# usb.net
KiCad netlist of a schematic drawn in Altium Designer
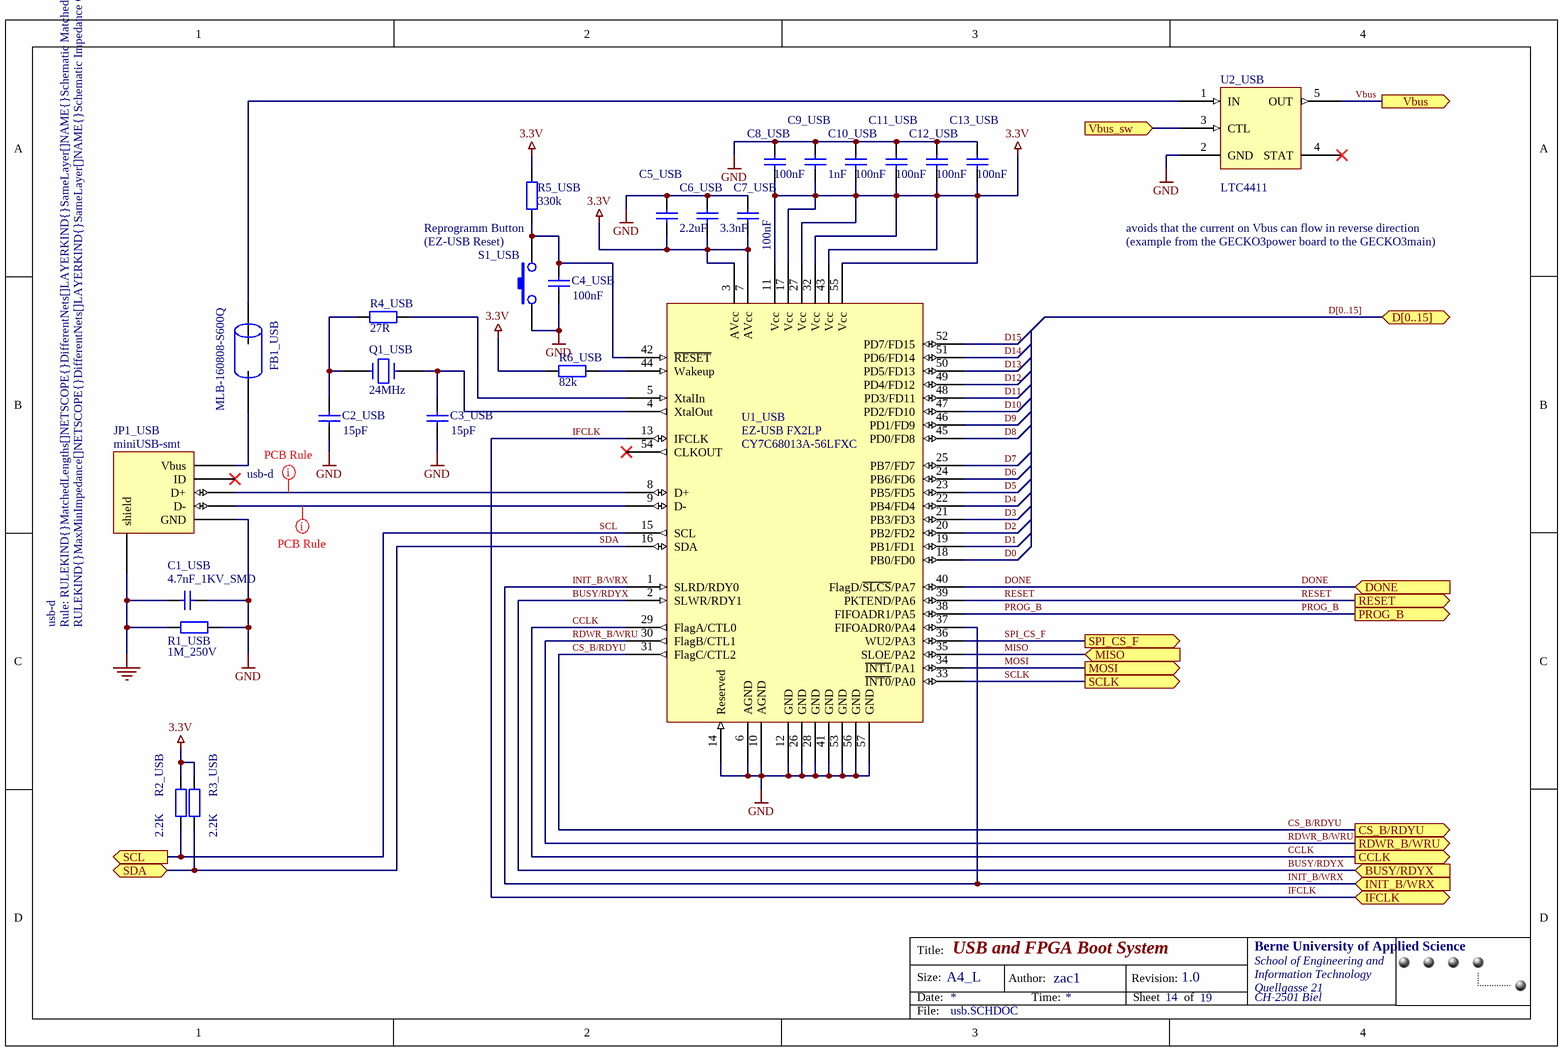
[diagram p0: usb.SCHDOC]

(export (version "E")
  (design (tool "Eeschema 10.0.6"))
  (components
    (comp (ref "C1_USB")
      (value "4.7nF_1KV_SMD")
      (footprint "CC3216-1206")
      (fields
        (field (name "MANUFACTURER") "AVX")
        (field (name "PART NUMBER") "1206AC472KAT1A")
        (field (name "Comment") "C")
      )
      (libsource (lib "gecko3-user") (part "C"))
    )
    (comp (ref "C2_USB")
      (value "15pF")
      (footprint "0402")
      (description "Ceramic Chip Capacitor - Standard")
      (fields
        (field (name "MANUFACTURER") "AVX")
        (field (name "PART NUMBER") "04025A150JAT2A")
        (field (name "PUBLISHER") "Altium Limited")
      )
      (libsource (lib "KEMET Chip Capacitor") (part "C0402"))
    )
    (comp (ref "C3_USB")
      (value "15pF")
      (footprint "0402")
      (description "Ceramic Chip Capacitor - Standard")
      (fields
        (field (name "MANUFACTURER") "AVX")
        (field (name "PART NUMBER") "04025A150JAT2A")
        (field (name "PUBLISHER") "Altium Limited")
      )
      (libsource (lib "KEMET Chip Capacitor") (part "C0402"))
    )
    (comp (ref "C4_USB")
      (value "100nF")
      (footprint "0402")
      (description "Ceramic Chip Capacitor - Standard")
      (fields
        (field (name "MANUFACTURER") "Murata")
        (field (name "PART NUMBER") "GRM155R71C104KA88D")
        (field (name "PUBLISHER") "Altium Limited")
      )
      (libsource (lib "KEMET Chip Capacitor") (part "C0402"))
    )
    (comp (ref "C5_USB")
      (value "2.2uF")
      (footprint "0805")
      (description "Capacitor")
      (fields
        (field (name "MANUFACTURER") "Murata")
        (field (name "PART NUMBER") "GRM21BR71A225KA01L")
        (field (name "PUBLISHER") "Altium Limited")
      )
      (libsource (lib "Miscellaneous Devices") (part "Cap"))
    )
    (comp (ref "C6_USB")
      (value "3.3nF")
      (footprint "0402")
      (description "Capacitor")
      (fields
        (field (name "MANUFACTURER") "PHYCOMP")
        (field (name "PART NUMBER") "2238 587 15629")
        (field (name "PUBLISHER") "Altium Limited")
      )
      (libsource (lib "Miscellaneous Devices") (part "Cap"))
    )
    (comp (ref "C7_USB")
      (value "100nF")
      (footprint "0402")
      (description "Capacitor")
      (fields
        (field (name "MANUFACTURER") "Murata")
        (field (name "PART NUMBER") "GRM155R71C104KA88D")
        (field (name "PUBLISHER") "Altium Limited")
      )
      (libsource (lib "Miscellaneous Devices") (part "Cap"))
    )
    (comp (ref "C8_USB")
      (value "100nF")
      (footprint "0402")
      (description "Capacitor")
      (fields
        (field (name "MANUFACTURER") "Murata")
        (field (name "PART NUMBER") "GRM155R71C104KA88D")
        (field (name "PUBLISHER") "Altium Limited")
      )
      (libsource (lib "Miscellaneous Devices") (part "Cap"))
    )
    (comp (ref "C9_USB")
      (value "1nF")
      (footprint "0402")
      (description "Capacitor")
      (fields
        (field (name "MANUFACTURER") "PHYCOMP")
        (field (name "PART NUMBER") "2238 587 15623")
        (field (name "PUBLISHER") "Altium Limited")
      )
      (libsource (lib "Miscellaneous Devices") (part "Cap"))
    )
    (comp (ref "C10_USB")
      (value "100nF")
      (footprint "0402")
      (description "Capacitor")
      (fields
        (field (name "MANUFACTURER") "Murata")
        (field (name "PART NUMBER") "GRM155R71C104KA88D")
        (field (name "PUBLISHER") "Altium Limited")
      )
      (libsource (lib "Miscellaneous Devices") (part "Cap"))
    )
    (comp (ref "C11_USB")
      (value "100nF")
      (footprint "0402")
      (description "Capacitor")
      (fields
        (field (name "MANUFACTURER") "Murata")
        (field (name "PART NUMBER") "GRM155R71C104KA88D")
        (field (name "PUBLISHER") "Altium Limited")
      )
      (libsource (lib "Miscellaneous Devices") (part "Cap"))
    )
    (comp (ref "C12_USB")
      (value "100nF")
      (footprint "0402")
      (description "Capacitor")
      (fields
        (field (name "MANUFACTURER") "Murata")
        (field (name "PART NUMBER") "GRM155R71C104KA88D")
        (field (name "PUBLISHER") "Altium Limited")
      )
      (libsource (lib "Miscellaneous Devices") (part "Cap"))
    )
    (comp (ref "C13_USB")
      (value "100nF")
      (footprint "0402")
      (description "Capacitor")
      (fields
        (field (name "MANUFACTURER") "Murata")
        (field (name "PART NUMBER") "GRM155R71C104KA88D")
        (field (name "PUBLISHER") "Altium Limited")
      )
      (libsource (lib "Miscellaneous Devices") (part "Cap"))
    )
    (comp (ref "FB1_USB")
      (value "MLB-160808-S600Q")
      (footprint "0603")
      (fields (field (name "MANUFACTURER") "Kitagawa") (field (name "Comment") "FERRITE-BEAD"))
      (libsource (lib "gecko3-user") (part "FERRITE-BEAD"))
    )
    (comp (ref "JP1_USB")
      (value "miniUSB-smt")
      (footprint "USB_MINI_B_SMD")
      (fields
        (field (name "MANUFACTURER") "Lumberg")
        (field (name "PART NUMBER") "2486 01")
        (field (name "Comment") "USB-MINIB-SMT")
      )
      (libsource (lib "gecko3-user") (part "USB-MINIB-SMT"))
    )
    (comp (ref "Q1_USB")
      (value "24MHz")
      (footprint "AT49")
      (description "SMD Quarz in the AT49 Case, like the ABLS series from Abracon")
      (fields
        (field (name "MANUFACTURER") "auris")
        (field (name "PART NUMBER") "Q-24.000M-HC49USSMD-F-30-50-D-30")
      )
      (libsource (lib "gecko3-user") (part "QUARZ-SMD"))
    )
    (comp (ref "R1_USB")
      (value "1M_250V")
      (footprint "CC3216-1206")
      (description "Resistor")
      (fields
        (field (name "MANUFACTURER") "Multicomp")
        (field (name "PART NUMBER") "MC 0.125W 1206 1% 1M")
        (field (name "PUBLISHER") "Altium Limited")
      )
      (libsource (lib "Miscellaneous Devices") (part "Res2"))
    )
    (comp (ref "R2_USB")
      (value "2.2K")
      (footprint "0402")
      (description "Resistor")
      (fields
        (field (name "MANUFACTURER") "PHYCOMP")
        (field (name "PART NUMBER") "232270672202")
        (field (name "PUBLISHER") "Altium Limited")
      )
      (libsource (lib "") (part "Res2_1"))
    )
    (comp (ref "R3_USB")
      (value "2.2K")
      (footprint "0402")
      (description "Resistor")
      (fields
        (field (name "MANUFACTURER") "PHYCOMP")
        (field (name "PART NUMBER") "232270672202")
        (field (name "PUBLISHER") "Altium Limited")
      )
      (libsource (lib "") (part "Res2_1"))
    )
    (comp (ref "R4_USB")
      (value "27R")
      (footprint "0402")
      (description "Resistor")
      (fields
        (field (name "MANUFACTURER") "PHYCOMP")
        (field (name "PART NUMBER") "232270672709")
        (field (name "PUBLISHER") "Altium Limited")
      )
      (libsource (lib "") (part "Res2_2"))
    )
    (comp (ref "R5_USB")
      (value "330k")
      (footprint "0402")
      (description "Resistor")
      (fields
        (field (name "MANUFACTURER") "PHYCOMP")
        (field (name "PART NUMBER") "232270673304")
        (field (name "PUBLISHER") "Altium Limited")
      )
      (libsource (lib "") (part "Res2_1"))
    )
    (comp (ref "R6_USB")
      (value "82k")
      (footprint "0402")
      (description "Resistor")
      (fields
        (field (name "MANUFACTURER") "PHYCOMP")
        (field (name "PART NUMBER") "232270678203")
        (field (name "PUBLISHER") "Altium Limited")
      )
      (libsource (lib "") (part "Res2_2"))
    )
    (comp (ref "S1_USB")
      (value "Reprogramm Button")
      (footprint "FSM")
      (fields (field (name "MANUFACTURER") "TYCO") (field (name "PART NUMBER") "0-1437565-1"))
      (libsource (lib "gecko3-user") (part "SW_PB"))
    )
    (comp (ref "U1_USB")
      (value "EZ-USB FX2LP")
      (footprint "QFN8x8")
      (fields
        (field (name "ALTIUM_VALUE") "CY7C68013A-56LFXC")
        (field (name "MANUFACTURER") "Cypress")
        (field (name "PART NUMBER") "CY7C68013A-56LFXC")
      )
      (libsource (lib "*") (part "EZ-USB-FX2_QFN"))
    )
    (comp (ref "U2_USB")
      (value "LTC4411")
      (footprint "TSOP-23-5")
      (fields (field (name "MANUFACTURER") "Linear") (field (name "PART NUMBER") "LTC4411ES5#PBF"))
      (libsource (lib "gecko3-user") (part "LTC4411"))
    )
  )
  (nets
    (net (code "1") (name "/BUSY{slash}RDYX") (class "Default")
      (node (ref "U1_USB") (pin "2") (pinfunction "SLWR/RDY1_2") (pintype "input"))
    )
    (net (code "2") (name "/CCLK") (class "Default")
      (node (ref "U1_USB") (pin "29") (pinfunction "FlagA/CTL0_29") (pintype "output"))
    )
    (net (code "3") (name "/CS_B{slash}RDYU") (class "Default")
      (node (ref "U1_USB") (pin "31") (pinfunction "FlagC/CTL2_31") (pintype "output"))
    )
    (net (code "4") (name "/D0") (class "Default")
      (node (ref "U1_USB") (pin "18") (pinfunction "PB0/FD0_18") (pintype "bidirectional"))
    )
    (net (code "5") (name "/D1") (class "Default")
      (node (ref "U1_USB") (pin "19") (pinfunction "PB1/FD1_19") (pintype "bidirectional"))
    )
    (net (code "6") (name "/D2") (class "Default")
      (node (ref "U1_USB") (pin "20") (pinfunction "PB2/FD2_20") (pintype "bidirectional"))
    )
    (net (code "7") (name "/D3") (class "Default")
      (node (ref "U1_USB") (pin "21") (pinfunction "PB3/FD3_21") (pintype "bidirectional"))
    )
    (net (code "8") (name "/D4") (class "Default")
      (node (ref "U1_USB") (pin "22") (pinfunction "PB4/FD4_22") (pintype "bidirectional"))
    )
    (net (code "9") (name "/D5") (class "Default")
      (node (ref "U1_USB") (pin "23") (pinfunction "PB5/FD5_23") (pintype "bidirectional"))
    )
    (net (code "10") (name "/D6") (class "Default")
      (node (ref "U1_USB") (pin "24") (pinfunction "PB6/FD6_24") (pintype "bidirectional"))
    )
    (net (code "11") (name "/D7") (class "Default")
      (node (ref "U1_USB") (pin "25") (pinfunction "PB7/FD7_25") (pintype "bidirectional"))
    )
    (net (code "12") (name "/D8") (class "Default")
      (node (ref "U1_USB") (pin "45") (pinfunction "PD0/FD8_45") (pintype "bidirectional"))
    )
    (net (code "13") (name "/D9") (class "Default")
      (node (ref "U1_USB") (pin "46") (pinfunction "PD1/FD9_46") (pintype "bidirectional"))
    )
    (net (code "14") (name "/D10") (class "Default")
      (node (ref "U1_USB") (pin "47") (pinfunction "PD2/FD10_47") (pintype "bidirectional"))
    )
    (net (code "15") (name "/D11") (class "Default")
      (node (ref "U1_USB") (pin "48") (pinfunction "PD3/FD11_48") (pintype "bidirectional"))
    )
    (net (code "16") (name "/D12") (class "Default")
      (node (ref "U1_USB") (pin "49") (pinfunction "PD4/FD12_49") (pintype "bidirectional"))
    )
    (net (code "17") (name "/D13") (class "Default")
      (node (ref "U1_USB") (pin "50") (pinfunction "PD5/FD13_50") (pintype "bidirectional"))
    )
    (net (code "18") (name "/D14") (class "Default")
      (node (ref "U1_USB") (pin "51") (pinfunction "PD6/FD14_51") (pintype "bidirectional"))
    )
    (net (code "19") (name "/D15") (class "Default")
      (node (ref "U1_USB") (pin "52") (pinfunction "PD7/FD15_52") (pintype "bidirectional"))
    )
    (net (code "20") (name "/DONE") (class "Default")
      (node (ref "U1_USB") (pin "40") (pinfunction "FlagD/~{SLCS}/PA7_40") (pintype "bidirectional"))
    )
    (net (code "22") (name "/IFCLK") (class "Default")
      (node (ref "U1_USB") (pin "13") (pinfunction "IFCLK_13") (pintype "bidirectional"))
    )
    (net (code "23") (name "/INIT_B{slash}WRX") (class "Default")
      (node (ref "U1_USB") (pin "1") (pinfunction "SLRD/RDY0_1") (pintype "input"))
      (node (ref "U1_USB") (pin "37") (pinfunction "FIFOADR0/PA4_37") (pintype "bidirectional"))
    )
    (net (code "24") (name "/MISO") (class "Default")
      (node (ref "U1_USB") (pin "35") (pinfunction "SLOE/PA2_35") (pintype "bidirectional"))
    )
    (net (code "25") (name "/MOSI") (class "Default")
      (node (ref "U1_USB") (pin "34") (pinfunction "~{INT1}/PA1_34") (pintype "bidirectional"))
    )
    (net (code "26") (name "/PROG_B") (class "Default")
      (node (ref "U1_USB") (pin "38") (pinfunction "FIFOADR1/PA5_38") (pintype "bidirectional"))
    )
    (net (code "27") (name "/RDWR_B{slash}WRU") (class "Default")
      (node (ref "U1_USB") (pin "30") (pinfunction "FlagB/CTL1_30") (pintype "output"))
    )
    (net (code "28") (name "/RESET") (class "Default")
      (node (ref "U1_USB") (pin "39") (pinfunction "PKTEND/PA6_39") (pintype "bidirectional"))
    )
    (net (code "29") (name "/SCL") (class "Default")
      (node (ref "R2_USB") (pin "1") (pinfunction "1_1") (pintype "passive"))
      (node (ref "U1_USB") (pin "15") (pinfunction "SCL_15") (pintype "output"))
    )
    (net (code "30") (name "/SCLK") (class "Default")
      (node (ref "U1_USB") (pin "33") (pinfunction "~{INT0}/PA0_33") (pintype "bidirectional"))
    )
    (net (code "31") (name "/SDA") (class "Default")
      (node (ref "R3_USB") (pin "1") (pinfunction "1_1") (pintype "passive"))
      (node (ref "U1_USB") (pin "16") (pinfunction "SDA_16") (pintype "bidirectional"))
    )
    (net (code "32") (name "/SPI_CS_F") (class "Default")
      (node (ref "U1_USB") (pin "36") (pinfunction "WU2/PA3_36") (pintype "bidirectional"))
    )
    (net (code "33") (name "/Vbus") (class "Default")
      (node (ref "U2_USB") (pin "5") (pinfunction "OUT_5") (pintype "output"))
    )
    (net (code "34") (name "/Vbus_sw") (class "Default")
      (node (ref "U2_USB") (pin "3") (pinfunction "CTL_3") (pintype "input"))
    )
    (net (code "35") (name "3.3V") (class "Default")
      (node (ref "C10_USB") (pin "1") (pinfunction "1_1") (pintype "passive"))
      (node (ref "C11_USB") (pin "1") (pinfunction "1_1") (pintype "passive"))
      (node (ref "C12_USB") (pin "1") (pinfunction "1_1") (pintype "passive"))
      (node (ref "C13_USB") (pin "1") (pinfunction "1_1") (pintype "passive"))
      (node (ref "C5_USB") (pin "1") (pinfunction "1_1") (pintype "passive"))
      (node (ref "C6_USB") (pin "1") (pinfunction "1_1") (pintype "passive"))
      (node (ref "C7_USB") (pin "1") (pinfunction "1_1") (pintype "passive"))
      (node (ref "C8_USB") (pin "1") (pinfunction "1_1") (pintype "passive"))
      (node (ref "C9_USB") (pin "1") (pinfunction "1_1") (pintype "passive"))
      (node (ref "R2_USB") (pin "2") (pinfunction "2_2") (pintype "passive"))
      (node (ref "R3_USB") (pin "2") (pinfunction "2_2") (pintype "passive"))
      (node (ref "R5_USB") (pin "2") (pinfunction "2_2") (pintype "passive"))
      (node (ref "R6_USB") (pin "2") (pinfunction "2_2") (pintype "passive"))
      (node (ref "U1_USB") (pin "11") (pinfunction "Vcc_11") (pintype "power_in"))
      (node (ref "U1_USB") (pin "17") (pinfunction "Vcc_17") (pintype "power_in"))
      (node (ref "U1_USB") (pin "27") (pinfunction "Vcc_27") (pintype "power_in"))
      (node (ref "U1_USB") (pin "3") (pinfunction "AVcc_3") (pintype "power_in"))
      (node (ref "U1_USB") (pin "32") (pinfunction "Vcc_32") (pintype "power_in"))
      (node (ref "U1_USB") (pin "43") (pinfunction "Vcc_43") (pintype "power_in"))
      (node (ref "U1_USB") (pin "55") (pinfunction "Vcc_55") (pintype "power_in"))
      (node (ref "U1_USB") (pin "7") (pinfunction "AVcc_7") (pintype "power_in"))
    )
    (net (code "36") (name "Earth") (class "Default")
      (node (ref "C1_USB") (pin "1") (pinfunction "1_1") (pintype "passive"))
      (node (ref "JP1_USB") (pin "shield") (pinfunction "shield_shield") (pintype "passive"))
      (node (ref "R1_USB") (pin "1") (pinfunction "1_1") (pintype "passive"))
    )
    (net (code "37") (name "GND") (class "Default")
      (node (ref "C10_USB") (pin "2") (pinfunction "2_2") (pintype "passive"))
      (node (ref "C11_USB") (pin "2") (pinfunction "2_2") (pintype "passive"))
      (node (ref "C12_USB") (pin "2") (pinfunction "2_2") (pintype "passive"))
      (node (ref "C13_USB") (pin "2") (pinfunction "2_2") (pintype "passive"))
      (node (ref "C1_USB") (pin "2") (pinfunction "2_2") (pintype "passive"))
      (node (ref "C2_USB") (pin "1") (pinfunction "1_1") (pintype "passive"))
      (node (ref "C3_USB") (pin "1") (pinfunction "1_1") (pintype "passive"))
      (node (ref "C4_USB") (pin "1") (pinfunction "1_1") (pintype "passive"))
      (node (ref "C5_USB") (pin "2") (pinfunction "2_2") (pintype "passive"))
      (node (ref "C6_USB") (pin "2") (pinfunction "2_2") (pintype "passive"))
      (node (ref "C7_USB") (pin "2") (pinfunction "2_2") (pintype "passive"))
      (node (ref "C8_USB") (pin "2") (pinfunction "2_2") (pintype "passive"))
      (node (ref "C9_USB") (pin "2") (pinfunction "2_2") (pintype "passive"))
      (node (ref "JP1_USB") (pin "GND") (pinfunction "GND_GND") (pintype "power_in"))
      (node (ref "R1_USB") (pin "2") (pinfunction "2_2") (pintype "passive"))
      (node (ref "S1_USB") (pin "1") (pinfunction "1_1") (pintype "passive"))
      (node (ref "U1_USB") (pin "10") (pinfunction "AGND_10") (pintype "power_in"))
      (node (ref "U1_USB") (pin "12") (pinfunction "GND_12") (pintype "power_in"))
      (node (ref "U1_USB") (pin "14") (pinfunction "Reserved_14") (pintype "input"))
      (node (ref "U1_USB") (pin "26") (pinfunction "GND_26") (pintype "power_in"))
      (node (ref "U1_USB") (pin "28") (pinfunction "GND_28") (pintype "power_in"))
      (node (ref "U1_USB") (pin "41") (pinfunction "GND_41") (pintype "power_in"))
      (node (ref "U1_USB") (pin "53") (pinfunction "GND_53") (pintype "power_in"))
      (node (ref "U1_USB") (pin "56") (pinfunction "GND_56") (pintype "power_in"))
      (node (ref "U1_USB") (pin "57") (pinfunction "GND_57") (pintype "power_in"))
      (node (ref "U1_USB") (pin "6") (pinfunction "AGND_6") (pintype "power_in"))
      (node (ref "U2_USB") (pin "2") (pinfunction "GND_2") (pintype "power_in"))
    )
    (net (code "38") (name "Net-(C2_USB-Pad2)") (class "Default")
      (node (ref "C2_USB") (pin "2") (pinfunction "2_2") (pintype "passive"))
      (node (ref "Q1_USB") (pin "1") (pinfunction "1_1") (pintype "passive"))
      (node (ref "R4_USB") (pin "2") (pinfunction "2_2") (pintype "passive"))
    )
    (net (code "39") (name "Net-(FB1_USB-Pad1)") (class "Default")
      (node (ref "FB1_USB") (pin "1") (pinfunction "1_1") (pintype "passive"))
      (node (ref "JP1_USB") (pin "Vbus") (pinfunction "Vbus_Vbus") (pintype "power_in"))
    )
    (net (code "40") (name "Net-(U1_USB-D+)") (class "Default")
      (node (ref "JP1_USB") (pin "D+") (pinfunction "D+_D+") (pintype "bidirectional"))
      (node (ref "U1_USB") (pin "8") (pinfunction "D+_8") (pintype "bidirectional"))
    )
    (net (code "41") (name "Net-(U1_USB-D-)") (class "Default")
      (node (ref "JP1_USB") (pin "D-") (pinfunction "D-_D-") (pintype "bidirectional"))
      (node (ref "U1_USB") (pin "9") (pinfunction "D-_9") (pintype "bidirectional"))
    )
    (net (code "42") (name "Net-(U1_USB-Wakeup)") (class "Default")
      (node (ref "R6_USB") (pin "1") (pinfunction "1_1") (pintype "passive"))
      (node (ref "U1_USB") (pin "44") (pinfunction "Wakeup_44") (pintype "input"))
    )
    (net (code "43") (name "Net-(U1_USB-XtalIn)") (class "Default")
      (node (ref "R4_USB") (pin "1") (pinfunction "1_1") (pintype "passive"))
      (node (ref "U1_USB") (pin "5") (pinfunction "XtalIn_5") (pintype "input"))
    )
    (net (code "44") (name "Net-(U1_USB-XtalOut)") (class "Default")
      (node (ref "C3_USB") (pin "2") (pinfunction "2_2") (pintype "passive"))
      (node (ref "Q1_USB") (pin "2") (pinfunction "2_2") (pintype "passive"))
      (node (ref "U1_USB") (pin "4") (pinfunction "XtalOut_4") (pintype "output"))
    )
    (net (code "45") (name "Net-(U1_USB-~{RESET})") (class "Default")
      (node (ref "C4_USB") (pin "2") (pinfunction "2_2") (pintype "passive"))
      (node (ref "R5_USB") (pin "1") (pinfunction "1_1") (pintype "passive"))
      (node (ref "S1_USB") (pin "2") (pinfunction "2_2") (pintype "passive"))
      (node (ref "U1_USB") (pin "42") (pinfunction "~{RESET}_42") (pintype "input"))
    )
    (net (code "46") (name "Net-(U2_USB-IN)") (class "Default")
      (node (ref "FB1_USB") (pin "2") (pinfunction "2_2") (pintype "passive"))
      (node (ref "U2_USB") (pin "1") (pinfunction "IN_1") (pintype "input"))
    )
    (net (code "47") (name "unconnected-(JP1_USB-PadID)") (class "Default")
      (node (ref "JP1_USB") (pin "ID") (pinfunction "ID_ID") (pintype "passive+no_connect"))
    )
    (net (code "48") (name "unconnected-(U1_USB-CLKOUT-Pad54)") (class "Default")
      (node (ref "U1_USB") (pin "54") (pinfunction "CLKOUT_54") (pintype "output+no_connect"))
    )
    (net (code "49") (name "unconnected-(U2_USB-STAT-Pad4)") (class "Default")
      (node (ref "U2_USB") (pin "4") (pinfunction "STAT_4") (pintype "open_collector+no_connect"))
    )
  )
)
